# peppermill.net
KiCad netlist of a schematic drawn in EAGLE
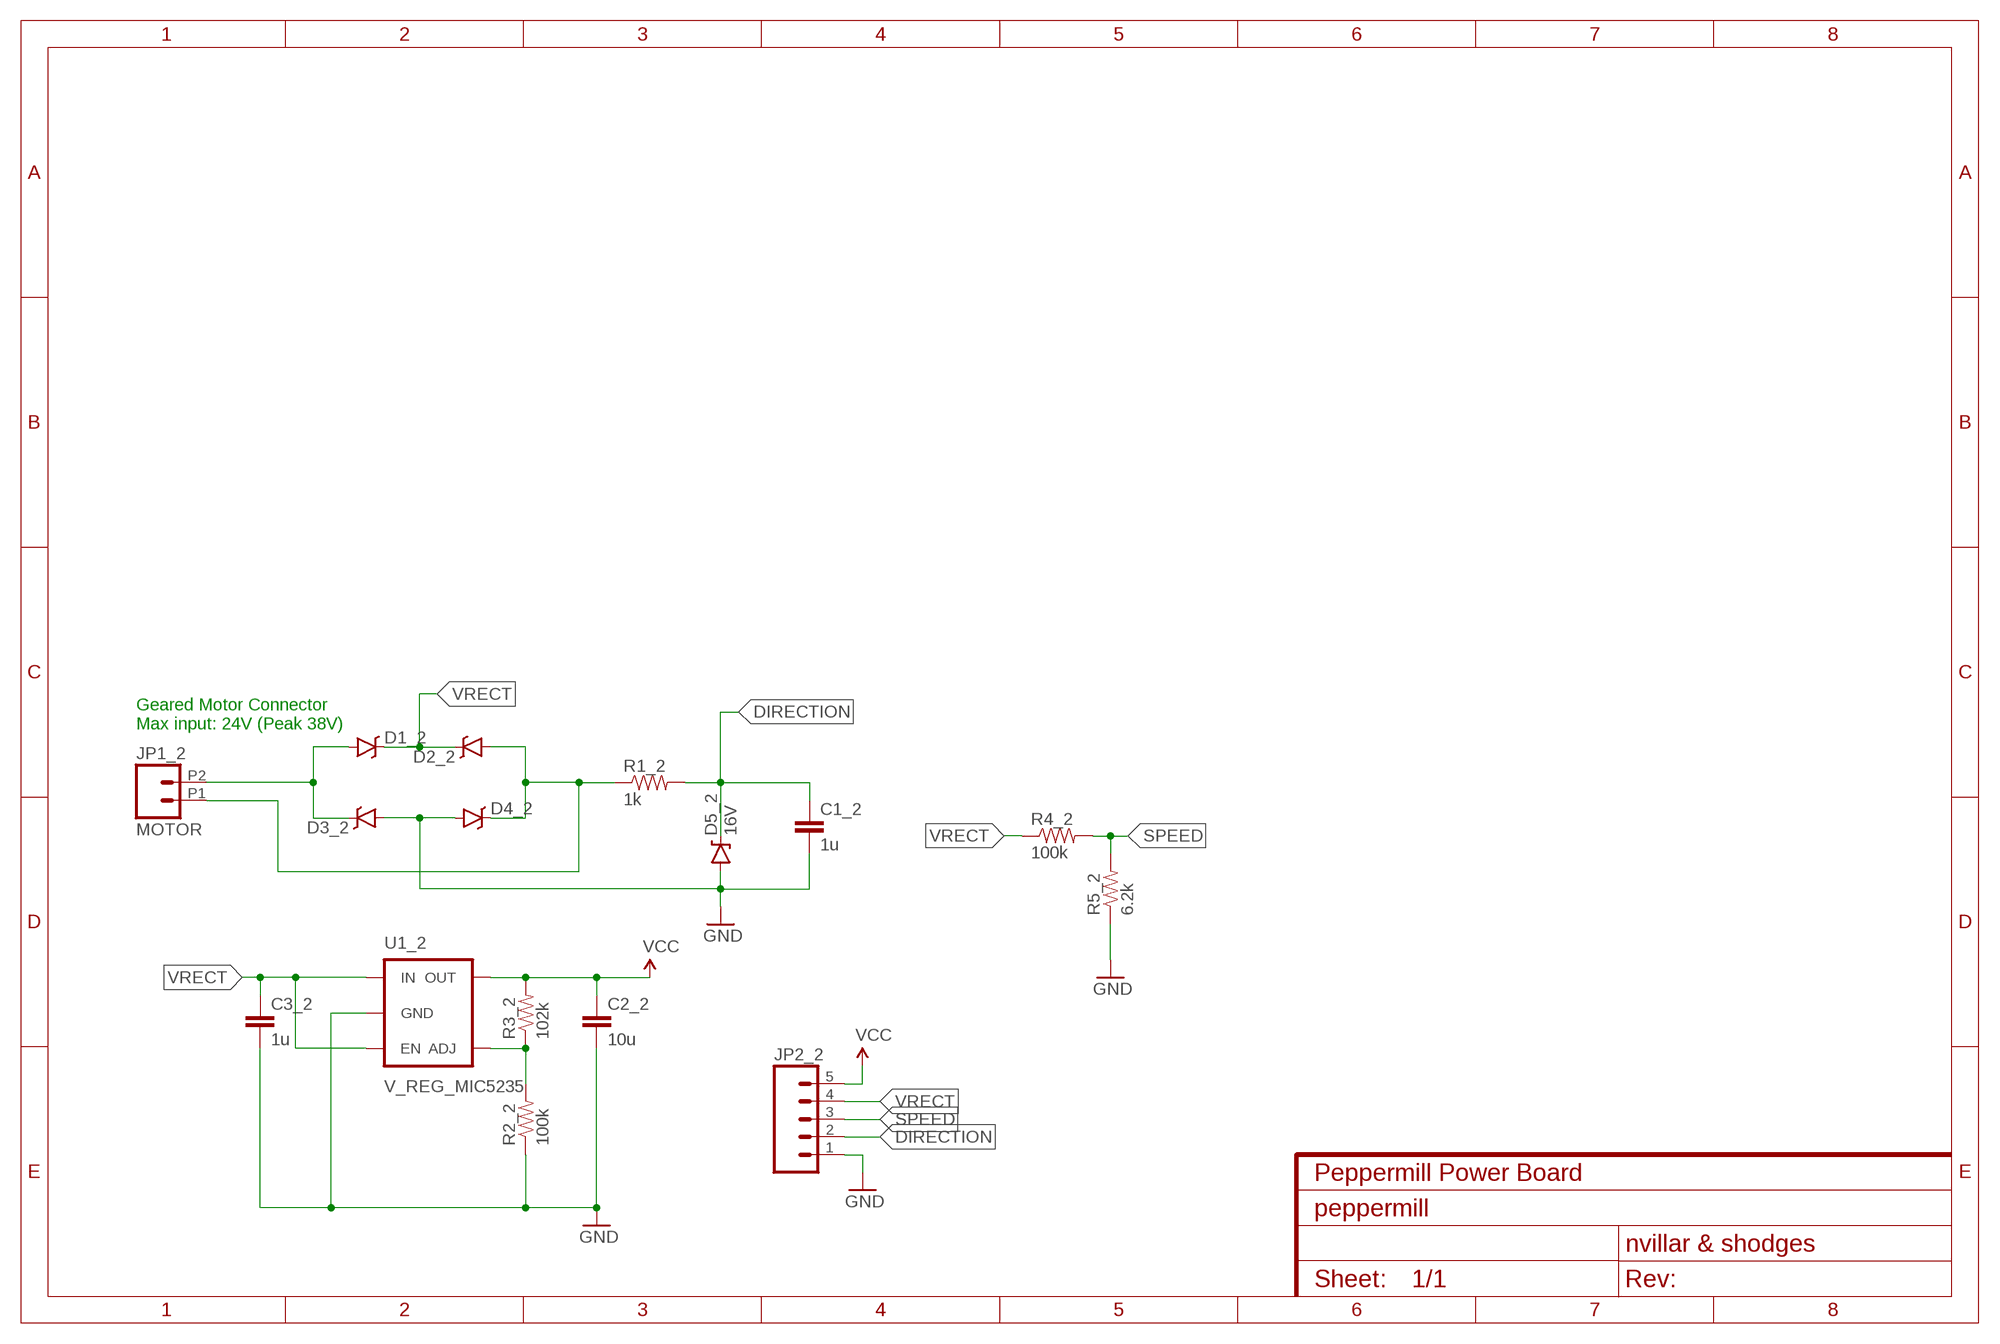
[diagram p0: schematic, sheet 1]

(export (version "E")
  (design (tool "Eeschema 10.0.6"))
  (components
    (comp (ref "C1_2")
      (value "1u")
      (footprint "eagle-import:0805")
      (libsource (lib "eagle-import") (part "CAP0805"))
    )
    (comp (ref "C2_2")
      (value "10u")
      (footprint "eagle-import:0805")
      (libsource (lib "eagle-import") (part "CAP0805"))
    )
    (comp (ref "C3_2")
      (value "1u")
      (footprint "eagle-import:0805")
      (libsource (lib "eagle-import") (part "CAP0805"))
    )
    (comp (ref "D1_2")
      (value "BAT20JFILM")
      (footprint "eagle-import:SOD-323")
      (libsource (lib "eagle-import") (part "BAT20JFILM"))
    )
    (comp (ref "D2_2")
      (value "BAT20JFILM")
      (footprint "eagle-import:SOD-323")
      (libsource (lib "eagle-import") (part "BAT20JFILM"))
    )
    (comp (ref "D3_2")
      (value "BAT20JFILM")
      (footprint "eagle-import:SOD-323")
      (libsource (lib "eagle-import") (part "BAT20JFILM"))
    )
    (comp (ref "D4_2")
      (value "BAT20JFILM")
      (footprint "eagle-import:SOD-323")
      (libsource (lib "eagle-import") (part "BAT20JFILM"))
    )
    (comp (ref "D5_2")
      (value "16V")
      (footprint "eagle-import:SOD-123")
      (libsource (lib "eagle-import") (part "DIODE-ZENER16V"))
    )
    (comp (ref "JP1_2")
      (value "MOTOR")
      (footprint "eagle-import:1X02_2.54_SCREWTERM")
      (libsource (lib "eagle-import") (part "M022.54MM_SCREWTERM"))
    )
    (comp (ref "JP2_2")
      (value "M05LOCK")
      (footprint "eagle-import:1X05_LOCK")
      (libsource (lib "eagle-import") (part "M05LOCK"))
    )
    (comp (ref "R1_2")
      (value "1k")
      (footprint "eagle-import:0805")
      (libsource (lib "eagle-import") (part "RESISTOR0805-RES"))
    )
    (comp (ref "R2_2")
      (value "100k")
      (footprint "eagle-import:0805")
      (libsource (lib "eagle-import") (part "RESISTOR0805-RES"))
    )
    (comp (ref "R3_2")
      (value "102k")
      (footprint "eagle-import:0805")
      (libsource (lib "eagle-import") (part "RESISTOR0805-RES"))
    )
    (comp (ref "R4_2")
      (value "100k")
      (footprint "eagle-import:0805")
      (libsource (lib "eagle-import") (part "RESISTOR0805-RES"))
    )
    (comp (ref "R5_2")
      (value "6.2k")
      (footprint "eagle-import:0805")
      (libsource (lib "eagle-import") (part "RESISTOR0805-RES"))
    )
    (comp (ref "U1_2")
      (value "V_REG_MIC5235")
      (footprint "eagle-import:SOT23-5")
      (libsource (lib "eagle-import") (part "V_REG_MIC5235"))
    )
  )
  (nets
    (net (code "1") (name "DIRECTION") (class "Default")
      (node (ref "C1_2") (pin "1") (pinfunction "1_1") (pintype "passive"))
      (node (ref "D5_2") (pin "C") (pinfunction "C_C") (pintype "passive"))
      (node (ref "JP2_2") (pin "2") (pinfunction "2_2") (pintype "passive"))
      (node (ref "R1_2") (pin "2") (pinfunction "2_2") (pintype "passive"))
    )
    (net (code "2") (name "GND") (class "Default")
      (node (ref "C1_2") (pin "2") (pinfunction "2_2") (pintype "passive"))
      (node (ref "C2_2") (pin "2") (pinfunction "2_2") (pintype "passive"))
      (node (ref "C3_2") (pin "2") (pinfunction "2_2") (pintype "passive"))
      (node (ref "D3_2") (pin "A") (pinfunction "A_A") (pintype "passive"))
      (node (ref "D4_2") (pin "A") (pinfunction "A_A") (pintype "passive"))
      (node (ref "D5_2") (pin "A") (pinfunction "A_A") (pintype "passive"))
      (node (ref "JP2_2") (pin "1") (pinfunction "1_1") (pintype "passive"))
      (node (ref "R2_2") (pin "1") (pinfunction "1_1") (pintype "passive"))
      (node (ref "R5_2") (pin "1") (pinfunction "1_1") (pintype "passive"))
      (node (ref "U1_2") (pin "2") (pinfunction "GND_2") (pintype "input"))
    )
    (net (code "3") (name "Net-(JP1_2-1)") (class "Default")
      (node (ref "D2_2") (pin "A") (pinfunction "A_A") (pintype "passive"))
      (node (ref "D4_2") (pin "C") (pinfunction "C_C") (pintype "passive"))
      (node (ref "JP1_2") (pin "P1") (pinfunction "1_P1") (pintype "passive"))
      (node (ref "R1_2") (pin "1") (pinfunction "1_1") (pintype "passive"))
    )
    (net (code "4") (name "Net-(JP1_2-2)") (class "Default")
      (node (ref "D1_2") (pin "A") (pinfunction "A_A") (pintype "passive"))
      (node (ref "D3_2") (pin "C") (pinfunction "C_C") (pintype "passive"))
      (node (ref "JP1_2") (pin "P2") (pinfunction "2_P2") (pintype "passive"))
    )
    (net (code "5") (name "Net-(U1_2-ADJ)") (class "Default")
      (node (ref "R2_2") (pin "2") (pinfunction "2_2") (pintype "passive"))
      (node (ref "R3_2") (pin "1") (pinfunction "1_1") (pintype "passive"))
      (node (ref "U1_2") (pin "4") (pinfunction "ADJ_4") (pintype "input"))
    )
    (net (code "6") (name "SPEED") (class "Default")
      (node (ref "JP2_2") (pin "3") (pinfunction "3_3") (pintype "passive"))
      (node (ref "R4_2") (pin "2") (pinfunction "2_2") (pintype "passive"))
      (node (ref "R5_2") (pin "2") (pinfunction "2_2") (pintype "passive"))
    )
    (net (code "7") (name "VCC") (class "Default")
      (node (ref "C2_2") (pin "1") (pinfunction "1_1") (pintype "passive"))
      (node (ref "JP2_2") (pin "5") (pinfunction "5_5") (pintype "passive"))
      (node (ref "R3_2") (pin "2") (pinfunction "2_2") (pintype "passive"))
      (node (ref "U1_2") (pin "5") (pinfunction "OUT_5") (pintype "passive"))
    )
    (net (code "8") (name "VRECT") (class "Default")
      (node (ref "C3_2") (pin "1") (pinfunction "1_1") (pintype "passive"))
      (node (ref "D1_2") (pin "C") (pinfunction "C_C") (pintype "passive"))
      (node (ref "D2_2") (pin "C") (pinfunction "C_C") (pintype "passive"))
      (node (ref "JP2_2") (pin "4") (pinfunction "4_4") (pintype "passive"))
      (node (ref "R4_2") (pin "1") (pinfunction "1_1") (pintype "passive"))
      (node (ref "U1_2") (pin "1") (pinfunction "IN_1") (pintype "input"))
      (node (ref "U1_2") (pin "3") (pinfunction "EN_3") (pintype "input"))
    )
  )
)
